# MB979.net
KiCad netlist of a schematic drawn in Altium Designer
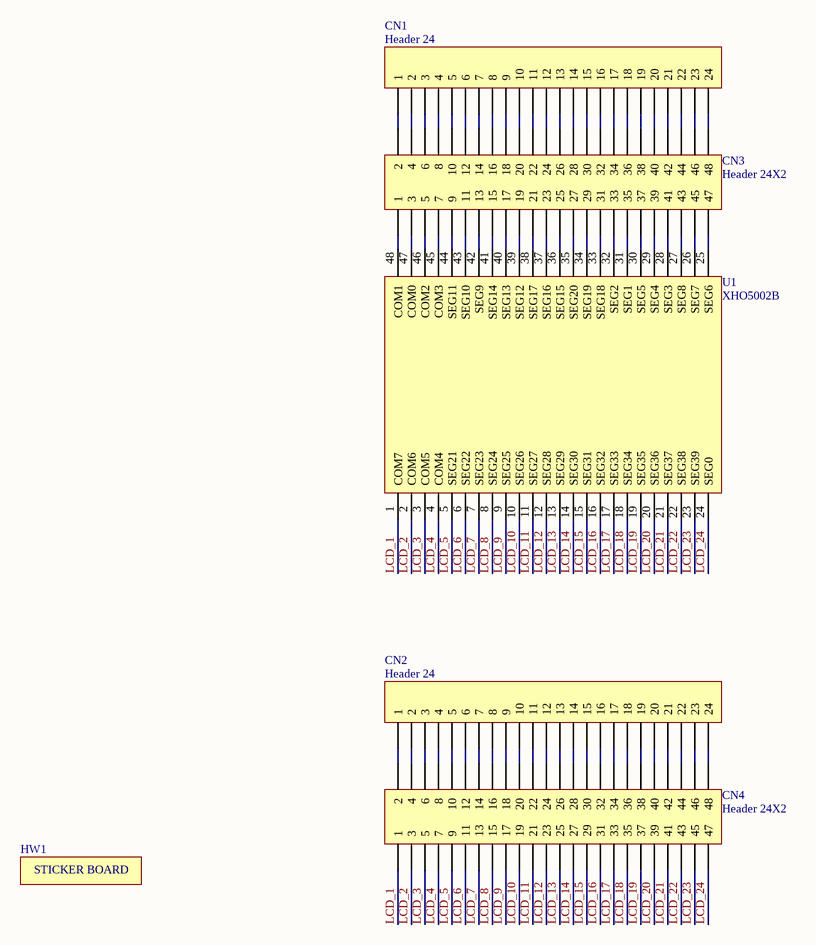
[diagram p0: MB979.SchDoc]

(export (version "E")
  (design (tool "Eeschema 10.0.6"))
  (components
    (comp (ref "CN1")
      (value "Header 24")
      (footprint "HDR1X24")
      (description "Header, 24-Pin")
      (fields (field (name "PUBLISHER") "Altium Limited"))
      (libsource (lib "Miscellaneous Connectors") (part "Header 24"))
    )
    (comp (ref "CN2")
      (value "Header 24")
      (footprint "HDR1X24")
      (description "Header, 24-Pin")
      (fields (field (name "PUBLISHER") "Altium Limited"))
      (libsource (lib "Miscellaneous Connectors") (part "Header 24"))
    )
    (comp (ref "CN3")
      (value "Header 24X2")
      (footprint "HDR2X24")
      (description "Header, 24-Pin, Dual row")
      (fields (field (name "PUBLISHER") "Altium Limited"))
      (libsource (lib "Miscellaneous Connectors") (part "Header 24X2"))
    )
    (comp (ref "CN4")
      (value "Header 24X2")
      (footprint "HDR2X24")
      (description "Header, 24-Pin, Dual row")
      (fields (field (name "PUBLISHER") "Altium Limited"))
      (libsource (lib "Miscellaneous Connectors") (part "Header 24X2"))
    )
    (comp (ref "HW1") (value "STICKER_BOARD") (libsource (lib "MB979") (part "STICKER_BOARD")))
    (comp (ref "U1") (value "XHO5002B") (libsource (lib "MB979") (part "XHO5002")))
  )
  (nets
    (net (code "1") (name "/LCD_1") (class "Default")
      (node (ref "CN4") (pin "1") (pinfunction "1_1") (pintype "passive"))
      (node (ref "U1") (pin "1") (pinfunction "COM7_1") (pintype "passive"))
    )
    (net (code "2") (name "/LCD_2") (class "Default")
      (node (ref "CN4") (pin "3") (pinfunction "3_3") (pintype "passive"))
      (node (ref "U1") (pin "2") (pinfunction "COM6_2") (pintype "passive"))
    )
    (net (code "3") (name "/LCD_3") (class "Default")
      (node (ref "CN4") (pin "5") (pinfunction "5_5") (pintype "passive"))
      (node (ref "U1") (pin "3") (pinfunction "COM5_3") (pintype "passive"))
    )
    (net (code "4") (name "/LCD_4") (class "Default")
      (node (ref "CN4") (pin "7") (pinfunction "7_7") (pintype "passive"))
      (node (ref "U1") (pin "4") (pinfunction "COM4_4") (pintype "passive"))
    )
    (net (code "5") (name "/LCD_5") (class "Default")
      (node (ref "CN4") (pin "9") (pinfunction "9_9") (pintype "passive"))
      (node (ref "U1") (pin "5") (pinfunction "SEG21_5") (pintype "passive"))
    )
    (net (code "6") (name "/LCD_6") (class "Default")
      (node (ref "CN4") (pin "11") (pinfunction "11_11") (pintype "passive"))
      (node (ref "U1") (pin "6") (pinfunction "SEG22_6") (pintype "passive"))
    )
    (net (code "7") (name "/LCD_7") (class "Default")
      (node (ref "CN4") (pin "13") (pinfunction "13_13") (pintype "passive"))
      (node (ref "U1") (pin "7") (pinfunction "SEG23_7") (pintype "passive"))
    )
    (net (code "8") (name "/LCD_8") (class "Default")
      (node (ref "CN4") (pin "15") (pinfunction "15_15") (pintype "passive"))
      (node (ref "U1") (pin "8") (pinfunction "SEG24_8") (pintype "passive"))
    )
    (net (code "9") (name "/LCD_9") (class "Default")
      (node (ref "CN4") (pin "17") (pinfunction "17_17") (pintype "passive"))
      (node (ref "U1") (pin "9") (pinfunction "SEG25_9") (pintype "passive"))
    )
    (net (code "10") (name "/LCD_10") (class "Default")
      (node (ref "CN4") (pin "19") (pinfunction "19_19") (pintype "passive"))
      (node (ref "U1") (pin "10") (pinfunction "SEG26_10") (pintype "passive"))
    )
    (net (code "11") (name "/LCD_11") (class "Default")
      (node (ref "CN4") (pin "21") (pinfunction "21_21") (pintype "passive"))
      (node (ref "U1") (pin "11") (pinfunction "SEG27_11") (pintype "passive"))
    )
    (net (code "12") (name "/LCD_12") (class "Default")
      (node (ref "CN4") (pin "23") (pinfunction "23_23") (pintype "passive"))
      (node (ref "U1") (pin "12") (pinfunction "SEG28_12") (pintype "passive"))
    )
    (net (code "13") (name "/LCD_13") (class "Default")
      (node (ref "CN4") (pin "25") (pinfunction "25_25") (pintype "passive"))
      (node (ref "U1") (pin "13") (pinfunction "SEG29_13") (pintype "passive"))
    )
    (net (code "14") (name "/LCD_14") (class "Default")
      (node (ref "CN4") (pin "27") (pinfunction "27_27") (pintype "passive"))
      (node (ref "U1") (pin "14") (pinfunction "SEG30_14") (pintype "passive"))
    )
    (net (code "15") (name "/LCD_15") (class "Default")
      (node (ref "CN4") (pin "29") (pinfunction "29_29") (pintype "passive"))
      (node (ref "U1") (pin "15") (pinfunction "SEG31_15") (pintype "passive"))
    )
    (net (code "16") (name "/LCD_16") (class "Default")
      (node (ref "CN4") (pin "31") (pinfunction "31_31") (pintype "passive"))
      (node (ref "U1") (pin "16") (pinfunction "SEG32_16") (pintype "passive"))
    )
    (net (code "17") (name "/LCD_17") (class "Default")
      (node (ref "CN4") (pin "33") (pinfunction "33_33") (pintype "passive"))
      (node (ref "U1") (pin "17") (pinfunction "SEG33_17") (pintype "passive"))
    )
    (net (code "18") (name "/LCD_18") (class "Default")
      (node (ref "CN4") (pin "35") (pinfunction "35_35") (pintype "passive"))
      (node (ref "U1") (pin "18") (pinfunction "SEG34_18") (pintype "passive"))
    )
    (net (code "19") (name "/LCD_19") (class "Default")
      (node (ref "CN4") (pin "37") (pinfunction "37_37") (pintype "passive"))
      (node (ref "U1") (pin "19") (pinfunction "SEG35_19") (pintype "passive"))
    )
    (net (code "20") (name "/LCD_20") (class "Default")
      (node (ref "CN4") (pin "39") (pinfunction "39_39") (pintype "passive"))
      (node (ref "U1") (pin "20") (pinfunction "SEG36_20") (pintype "passive"))
    )
    (net (code "21") (name "/LCD_21") (class "Default")
      (node (ref "CN4") (pin "41") (pinfunction "41_41") (pintype "passive"))
      (node (ref "U1") (pin "21") (pinfunction "SEG37_21") (pintype "passive"))
    )
    (net (code "22") (name "/LCD_22") (class "Default")
      (node (ref "CN4") (pin "43") (pinfunction "43_43") (pintype "passive"))
      (node (ref "U1") (pin "22") (pinfunction "SEG38_22") (pintype "passive"))
    )
    (net (code "23") (name "/LCD_23") (class "Default")
      (node (ref "CN4") (pin "45") (pinfunction "45_45") (pintype "passive"))
      (node (ref "U1") (pin "23") (pinfunction "SEG39_23") (pintype "passive"))
    )
    (net (code "24") (name "/LCD_24") (class "Default")
      (node (ref "CN4") (pin "47") (pinfunction "47_47") (pintype "passive"))
      (node (ref "U1") (pin "24") (pinfunction "SEG0_24") (pintype "passive"))
    )
    (net (code "25") (name "Net-(CN1-Pad1)") (class "Default")
      (node (ref "CN1") (pin "1") (pinfunction "1_1") (pintype "passive"))
      (node (ref "CN3") (pin "2") (pinfunction "2_2") (pintype "passive"))
    )
    (net (code "26") (name "Net-(CN1-Pad2)") (class "Default")
      (node (ref "CN1") (pin "2") (pinfunction "2_2") (pintype "passive"))
      (node (ref "CN3") (pin "4") (pinfunction "4_4") (pintype "passive"))
    )
    (net (code "27") (name "Net-(CN1-Pad3)") (class "Default")
      (node (ref "CN1") (pin "3") (pinfunction "3_3") (pintype "passive"))
      (node (ref "CN3") (pin "6") (pinfunction "6_6") (pintype "passive"))
    )
    (net (code "28") (name "Net-(CN1-Pad4)") (class "Default")
      (node (ref "CN1") (pin "4") (pinfunction "4_4") (pintype "passive"))
      (node (ref "CN3") (pin "8") (pinfunction "8_8") (pintype "passive"))
    )
    (net (code "29") (name "Net-(CN1-Pad5)") (class "Default")
      (node (ref "CN1") (pin "5") (pinfunction "5_5") (pintype "passive"))
      (node (ref "CN3") (pin "10") (pinfunction "10_10") (pintype "passive"))
    )
    (net (code "30") (name "Net-(CN1-Pad6)") (class "Default")
      (node (ref "CN1") (pin "6") (pinfunction "6_6") (pintype "passive"))
      (node (ref "CN3") (pin "12") (pinfunction "12_12") (pintype "passive"))
    )
    (net (code "31") (name "Net-(CN1-Pad7)") (class "Default")
      (node (ref "CN1") (pin "7") (pinfunction "7_7") (pintype "passive"))
      (node (ref "CN3") (pin "14") (pinfunction "14_14") (pintype "passive"))
    )
    (net (code "32") (name "Net-(CN1-Pad8)") (class "Default")
      (node (ref "CN1") (pin "8") (pinfunction "8_8") (pintype "passive"))
      (node (ref "CN3") (pin "16") (pinfunction "16_16") (pintype "passive"))
    )
    (net (code "33") (name "Net-(CN1-Pad9)") (class "Default")
      (node (ref "CN1") (pin "9") (pinfunction "9_9") (pintype "passive"))
      (node (ref "CN3") (pin "18") (pinfunction "18_18") (pintype "passive"))
    )
    (net (code "34") (name "Net-(CN1-Pad10)") (class "Default")
      (node (ref "CN1") (pin "10") (pinfunction "10_10") (pintype "passive"))
      (node (ref "CN3") (pin "20") (pinfunction "20_20") (pintype "passive"))
    )
    (net (code "35") (name "Net-(CN1-Pad11)") (class "Default")
      (node (ref "CN1") (pin "11") (pinfunction "11_11") (pintype "passive"))
      (node (ref "CN3") (pin "22") (pinfunction "22_22") (pintype "passive"))
    )
    (net (code "36") (name "Net-(CN1-Pad12)") (class "Default")
      (node (ref "CN1") (pin "12") (pinfunction "12_12") (pintype "passive"))
      (node (ref "CN3") (pin "24") (pinfunction "24_24") (pintype "passive"))
    )
    (net (code "37") (name "Net-(CN1-Pad13)") (class "Default")
      (node (ref "CN1") (pin "13") (pinfunction "13_13") (pintype "passive"))
      (node (ref "CN3") (pin "26") (pinfunction "26_26") (pintype "passive"))
    )
    (net (code "38") (name "Net-(CN1-Pad14)") (class "Default")
      (node (ref "CN1") (pin "14") (pinfunction "14_14") (pintype "passive"))
      (node (ref "CN3") (pin "28") (pinfunction "28_28") (pintype "passive"))
    )
    (net (code "39") (name "Net-(CN1-Pad15)") (class "Default")
      (node (ref "CN1") (pin "15") (pinfunction "15_15") (pintype "passive"))
      (node (ref "CN3") (pin "30") (pinfunction "30_30") (pintype "passive"))
    )
    (net (code "40") (name "Net-(CN1-Pad16)") (class "Default")
      (node (ref "CN1") (pin "16") (pinfunction "16_16") (pintype "passive"))
      (node (ref "CN3") (pin "32") (pinfunction "32_32") (pintype "passive"))
    )
    (net (code "41") (name "Net-(CN1-Pad17)") (class "Default")
      (node (ref "CN1") (pin "17") (pinfunction "17_17") (pintype "passive"))
      (node (ref "CN3") (pin "34") (pinfunction "34_34") (pintype "passive"))
    )
    (net (code "42") (name "Net-(CN1-Pad18)") (class "Default")
      (node (ref "CN1") (pin "18") (pinfunction "18_18") (pintype "passive"))
      (node (ref "CN3") (pin "36") (pinfunction "36_36") (pintype "passive"))
    )
    (net (code "43") (name "Net-(CN1-Pad19)") (class "Default")
      (node (ref "CN1") (pin "19") (pinfunction "19_19") (pintype "passive"))
      (node (ref "CN3") (pin "38") (pinfunction "38_38") (pintype "passive"))
    )
    (net (code "44") (name "Net-(CN1-Pad20)") (class "Default")
      (node (ref "CN1") (pin "20") (pinfunction "20_20") (pintype "passive"))
      (node (ref "CN3") (pin "40") (pinfunction "40_40") (pintype "passive"))
    )
    (net (code "45") (name "Net-(CN1-Pad21)") (class "Default")
      (node (ref "CN1") (pin "21") (pinfunction "21_21") (pintype "passive"))
      (node (ref "CN3") (pin "42") (pinfunction "42_42") (pintype "passive"))
    )
    (net (code "46") (name "Net-(CN1-Pad22)") (class "Default")
      (node (ref "CN1") (pin "22") (pinfunction "22_22") (pintype "passive"))
      (node (ref "CN3") (pin "44") (pinfunction "44_44") (pintype "passive"))
    )
    (net (code "47") (name "Net-(CN1-Pad23)") (class "Default")
      (node (ref "CN1") (pin "23") (pinfunction "23_23") (pintype "passive"))
      (node (ref "CN3") (pin "46") (pinfunction "46_46") (pintype "passive"))
    )
    (net (code "48") (name "Net-(CN1-Pad24)") (class "Default")
      (node (ref "CN1") (pin "24") (pinfunction "24_24") (pintype "passive"))
      (node (ref "CN3") (pin "48") (pinfunction "48_48") (pintype "passive"))
    )
    (net (code "49") (name "Net-(CN2-Pad1)") (class "Default")
      (node (ref "CN2") (pin "1") (pinfunction "1_1") (pintype "passive"))
      (node (ref "CN4") (pin "2") (pinfunction "2_2") (pintype "passive"))
    )
    (net (code "50") (name "Net-(CN2-Pad2)") (class "Default")
      (node (ref "CN2") (pin "2") (pinfunction "2_2") (pintype "passive"))
      (node (ref "CN4") (pin "4") (pinfunction "4_4") (pintype "passive"))
    )
    (net (code "51") (name "Net-(CN2-Pad3)") (class "Default")
      (node (ref "CN2") (pin "3") (pinfunction "3_3") (pintype "passive"))
      (node (ref "CN4") (pin "6") (pinfunction "6_6") (pintype "passive"))
    )
    (net (code "52") (name "Net-(CN2-Pad4)") (class "Default")
      (node (ref "CN2") (pin "4") (pinfunction "4_4") (pintype "passive"))
      (node (ref "CN4") (pin "8") (pinfunction "8_8") (pintype "passive"))
    )
    (net (code "53") (name "Net-(CN2-Pad5)") (class "Default")
      (node (ref "CN2") (pin "5") (pinfunction "5_5") (pintype "passive"))
      (node (ref "CN4") (pin "10") (pinfunction "10_10") (pintype "passive"))
    )
    (net (code "54") (name "Net-(CN2-Pad6)") (class "Default")
      (node (ref "CN2") (pin "6") (pinfunction "6_6") (pintype "passive"))
      (node (ref "CN4") (pin "12") (pinfunction "12_12") (pintype "passive"))
    )
    (net (code "55") (name "Net-(CN2-Pad7)") (class "Default")
      (node (ref "CN2") (pin "7") (pinfunction "7_7") (pintype "passive"))
      (node (ref "CN4") (pin "14") (pinfunction "14_14") (pintype "passive"))
    )
    (net (code "56") (name "Net-(CN2-Pad8)") (class "Default")
      (node (ref "CN2") (pin "8") (pinfunction "8_8") (pintype "passive"))
      (node (ref "CN4") (pin "16") (pinfunction "16_16") (pintype "passive"))
    )
    (net (code "57") (name "Net-(CN2-Pad9)") (class "Default")
      (node (ref "CN2") (pin "9") (pinfunction "9_9") (pintype "passive"))
      (node (ref "CN4") (pin "18") (pinfunction "18_18") (pintype "passive"))
    )
    (net (code "58") (name "Net-(CN2-Pad10)") (class "Default")
      (node (ref "CN2") (pin "10") (pinfunction "10_10") (pintype "passive"))
      (node (ref "CN4") (pin "20") (pinfunction "20_20") (pintype "passive"))
    )
    (net (code "59") (name "Net-(CN2-Pad11)") (class "Default")
      (node (ref "CN2") (pin "11") (pinfunction "11_11") (pintype "passive"))
      (node (ref "CN4") (pin "22") (pinfunction "22_22") (pintype "passive"))
    )
    (net (code "60") (name "Net-(CN2-Pad12)") (class "Default")
      (node (ref "CN2") (pin "12") (pinfunction "12_12") (pintype "passive"))
      (node (ref "CN4") (pin "24") (pinfunction "24_24") (pintype "passive"))
    )
    (net (code "61") (name "Net-(CN2-Pad13)") (class "Default")
      (node (ref "CN2") (pin "13") (pinfunction "13_13") (pintype "passive"))
      (node (ref "CN4") (pin "26") (pinfunction "26_26") (pintype "passive"))
    )
    (net (code "62") (name "Net-(CN2-Pad14)") (class "Default")
      (node (ref "CN2") (pin "14") (pinfunction "14_14") (pintype "passive"))
      (node (ref "CN4") (pin "28") (pinfunction "28_28") (pintype "passive"))
    )
    (net (code "63") (name "Net-(CN2-Pad15)") (class "Default")
      (node (ref "CN2") (pin "15") (pinfunction "15_15") (pintype "passive"))
      (node (ref "CN4") (pin "30") (pinfunction "30_30") (pintype "passive"))
    )
    (net (code "64") (name "Net-(CN2-Pad16)") (class "Default")
      (node (ref "CN2") (pin "16") (pinfunction "16_16") (pintype "passive"))
      (node (ref "CN4") (pin "32") (pinfunction "32_32") (pintype "passive"))
    )
    (net (code "65") (name "Net-(CN2-Pad17)") (class "Default")
      (node (ref "CN2") (pin "17") (pinfunction "17_17") (pintype "passive"))
      (node (ref "CN4") (pin "34") (pinfunction "34_34") (pintype "passive"))
    )
    (net (code "66") (name "Net-(CN2-Pad18)") (class "Default")
      (node (ref "CN2") (pin "18") (pinfunction "18_18") (pintype "passive"))
      (node (ref "CN4") (pin "36") (pinfunction "36_36") (pintype "passive"))
    )
    (net (code "67") (name "Net-(CN2-Pad19)") (class "Default")
      (node (ref "CN2") (pin "19") (pinfunction "19_19") (pintype "passive"))
      (node (ref "CN4") (pin "38") (pinfunction "38_38") (pintype "passive"))
    )
    (net (code "68") (name "Net-(CN2-Pad20)") (class "Default")
      (node (ref "CN2") (pin "20") (pinfunction "20_20") (pintype "passive"))
      (node (ref "CN4") (pin "40") (pinfunction "40_40") (pintype "passive"))
    )
    (net (code "69") (name "Net-(CN2-Pad21)") (class "Default")
      (node (ref "CN2") (pin "21") (pinfunction "21_21") (pintype "passive"))
      (node (ref "CN4") (pin "42") (pinfunction "42_42") (pintype "passive"))
    )
    (net (code "70") (name "Net-(CN2-Pad22)") (class "Default")
      (node (ref "CN2") (pin "22") (pinfunction "22_22") (pintype "passive"))
      (node (ref "CN4") (pin "44") (pinfunction "44_44") (pintype "passive"))
    )
    (net (code "71") (name "Net-(CN2-Pad23)") (class "Default")
      (node (ref "CN2") (pin "23") (pinfunction "23_23") (pintype "passive"))
      (node (ref "CN4") (pin "46") (pinfunction "46_46") (pintype "passive"))
    )
    (net (code "72") (name "Net-(CN2-Pad24)") (class "Default")
      (node (ref "CN2") (pin "24") (pinfunction "24_24") (pintype "passive"))
      (node (ref "CN4") (pin "48") (pinfunction "48_48") (pintype "passive"))
    )
    (net (code "73") (name "Net-(U1-COM0)") (class "Default")
      (node (ref "CN3") (pin "3") (pinfunction "3_3") (pintype "passive"))
      (node (ref "U1") (pin "47") (pinfunction "COM0_47") (pintype "passive"))
    )
    (net (code "74") (name "Net-(U1-COM1)") (class "Default")
      (node (ref "CN3") (pin "1") (pinfunction "1_1") (pintype "passive"))
      (node (ref "U1") (pin "48") (pinfunction "COM1_48") (pintype "passive"))
    )
    (net (code "75") (name "Net-(U1-COM2)") (class "Default")
      (node (ref "CN3") (pin "5") (pinfunction "5_5") (pintype "passive"))
      (node (ref "U1") (pin "46") (pinfunction "COM2_46") (pintype "passive"))
    )
    (net (code "76") (name "Net-(U1-COM3)") (class "Default")
      (node (ref "CN3") (pin "7") (pinfunction "7_7") (pintype "passive"))
      (node (ref "U1") (pin "45") (pinfunction "COM3_45") (pintype "passive"))
    )
    (net (code "77") (name "Net-(U1-SEG1)") (class "Default")
      (node (ref "CN3") (pin "35") (pinfunction "35_35") (pintype "passive"))
      (node (ref "U1") (pin "31") (pinfunction "SEG1_31") (pintype "passive"))
    )
    (net (code "78") (name "Net-(U1-SEG2)") (class "Default")
      (node (ref "CN3") (pin "33") (pinfunction "33_33") (pintype "passive"))
      (node (ref "U1") (pin "32") (pinfunction "SEG2_32") (pintype "passive"))
    )
    (net (code "79") (name "Net-(U1-SEG3)") (class "Default")
      (node (ref "CN3") (pin "41") (pinfunction "41_41") (pintype "passive"))
      (node (ref "U1") (pin "28") (pinfunction "SEG3_28") (pintype "passive"))
    )
    (net (code "80") (name "Net-(U1-SEG4)") (class "Default")
      (node (ref "CN3") (pin "39") (pinfunction "39_39") (pintype "passive"))
      (node (ref "U1") (pin "29") (pinfunction "SEG4_29") (pintype "passive"))
    )
    (net (code "81") (name "Net-(U1-SEG5)") (class "Default")
      (node (ref "CN3") (pin "37") (pinfunction "37_37") (pintype "passive"))
      (node (ref "U1") (pin "30") (pinfunction "SEG5_30") (pintype "passive"))
    )
    (net (code "82") (name "Net-(U1-SEG6)") (class "Default")
      (node (ref "CN3") (pin "47") (pinfunction "47_47") (pintype "passive"))
      (node (ref "U1") (pin "25") (pinfunction "SEG6_25") (pintype "passive"))
    )
    (net (code "83") (name "Net-(U1-SEG7)") (class "Default")
      (node (ref "CN3") (pin "45") (pinfunction "45_45") (pintype "passive"))
      (node (ref "U1") (pin "26") (pinfunction "SEG7_26") (pintype "passive"))
    )
    (net (code "84") (name "Net-(U1-SEG8)") (class "Default")
      (node (ref "CN3") (pin "43") (pinfunction "43_43") (pintype "passive"))
      (node (ref "U1") (pin "27") (pinfunction "SEG8_27") (pintype "passive"))
    )
    (net (code "85") (name "Net-(U1-SEG9)") (class "Default")
      (node (ref "CN3") (pin "13") (pinfunction "13_13") (pintype "passive"))
      (node (ref "U1") (pin "42") (pinfunction "SEG9_42") (pintype "passive"))
    )
    (net (code "86") (name "Net-(U1-SEG10)") (class "Default")
      (node (ref "CN3") (pin "11") (pinfunction "11_11") (pintype "passive"))
      (node (ref "U1") (pin "43") (pinfunction "SEG10_43") (pintype "passive"))
    )
    (net (code "87") (name "Net-(U1-SEG11)") (class "Default")
      (node (ref "CN3") (pin "9") (pinfunction "9_9") (pintype "passive"))
      (node (ref "U1") (pin "44") (pinfunction "SEG11_44") (pintype "passive"))
    )
    (net (code "88") (name "Net-(U1-SEG12)") (class "Default")
      (node (ref "CN3") (pin "19") (pinfunction "19_19") (pintype "passive"))
      (node (ref "U1") (pin "39") (pinfunction "SEG12_39") (pintype "passive"))
    )
    (net (code "89") (name "Net-(U1-SEG13)") (class "Default")
      (node (ref "CN3") (pin "17") (pinfunction "17_17") (pintype "passive"))
      (node (ref "U1") (pin "40") (pinfunction "SEG13_40") (pintype "passive"))
    )
    (net (code "90") (name "Net-(U1-SEG14)") (class "Default")
      (node (ref "CN3") (pin "15") (pinfunction "15_15") (pintype "passive"))
      (node (ref "U1") (pin "41") (pinfunction "SEG14_41") (pintype "passive"))
    )
    (net (code "91") (name "Net-(U1-SEG15)") (class "Default")
      (node (ref "CN3") (pin "25") (pinfunction "25_25") (pintype "passive"))
      (node (ref "U1") (pin "36") (pinfunction "SEG15_36") (pintype "passive"))
    )
    (net (code "92") (name "Net-(U1-SEG16)") (class "Default")
      (node (ref "CN3") (pin "23") (pinfunction "23_23") (pintype "passive"))
      (node (ref "U1") (pin "37") (pinfunction "SEG16_37") (pintype "passive"))
    )
    (net (code "93") (name "Net-(U1-SEG17)") (class "Default")
      (node (ref "CN3") (pin "21") (pinfunction "21_21") (pintype "passive"))
      (node (ref "U1") (pin "38") (pinfunction "SEG17_38") (pintype "passive"))
    )
    (net (code "94") (name "Net-(U1-SEG18)") (class "Default")
      (node (ref "CN3") (pin "31") (pinfunction "31_31") (pintype "passive"))
      (node (ref "U1") (pin "33") (pinfunction "SEG18_33") (pintype "passive"))
    )
    (net (code "95") (name "Net-(U1-SEG19)") (class "Default")
      (node (ref "CN3") (pin "29") (pinfunction "29_29") (pintype "passive"))
      (node (ref "U1") (pin "34") (pinfunction "SEG19_34") (pintype "passive"))
    )
    (net (code "96") (name "Net-(U1-SEG20)") (class "Default")
      (node (ref "CN3") (pin "27") (pinfunction "27_27") (pintype "passive"))
      (node (ref "U1") (pin "35") (pinfunction "SEG20_35") (pintype "passive"))
    )
  )
)
